# PCB-SSB-2x2.net
KiCad netlist of a schematic drawn in EAGLE
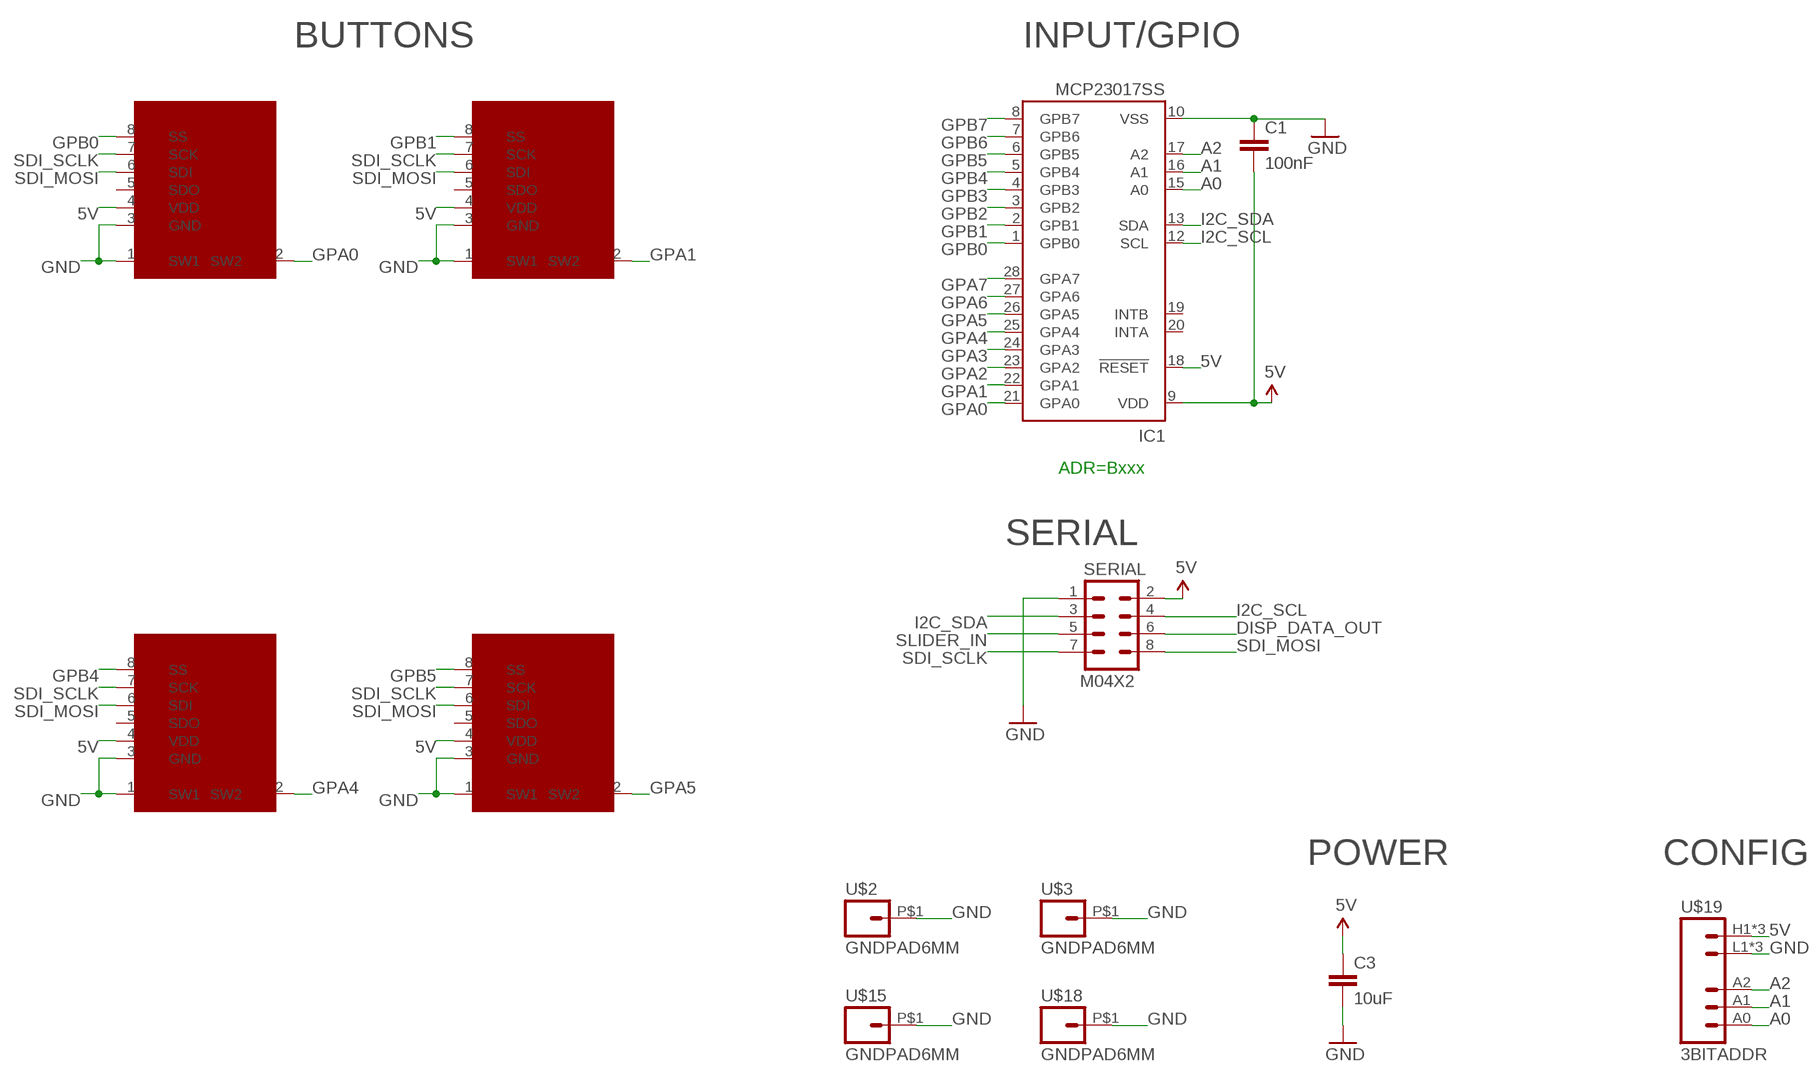
[diagram p0: schematic, sheet 1]

(export (version "E")
  (design (tool "Eeschema 10.0.6"))
  (components
    (comp (ref "C1")
      (value "100nF")
      (footprint "eagle-import:0603-CAP")
      (libsource (lib "eagle-import") (part "CAP0603-CAP"))
    )
    (comp (ref "C3")
      (value "10uF")
      (footprint "eagle-import:0805")
      (libsource (lib "eagle-import") (part "CAP0805"))
    )
    (comp (ref "IC1")
      (value "MCP23017SS")
      (footprint "eagle-import:SSOP28")
      (fields
        (field (name "MF") "MICROCHIP")
        (field (name "MPN") "MCP23017-E/SS")
        (field (name "MPN_1") "MCP23017-E/SS")
        (field (name "OC_FARNELL") "1467674")
        (field (name "OC_NEWARK") "31K2960")
      )
      (libsource (lib "eagle-import") (part "MCP23017SS"))
    )
    (comp (ref "SERIAL")
      (value "M04X2")
      (footprint "eagle-import:2X4")
      (libsource (lib "eagle-import") (part "M04X2"))
    )
    (comp (ref "SSW1")
      (value "SMART_SWITCHSMART_SWITCH_8PIN")
      (footprint "eagle-import:SMART_SWITCH")
      (libsource (lib "eagle-import") (part "SMART_SWITCHSMART_SWITCH_8PIN"))
    )
    (comp (ref "SSW2")
      (value "SMART_SWITCHSMART_SWITCH_8PIN")
      (footprint "eagle-import:SMART_SWITCH")
      (libsource (lib "eagle-import") (part "SMART_SWITCHSMART_SWITCH_8PIN"))
    )
    (comp (ref "SSW5")
      (value "SMART_SWITCHSMART_SWITCH_8PIN")
      (footprint "eagle-import:SMART_SWITCH")
      (libsource (lib "eagle-import") (part "SMART_SWITCHSMART_SWITCH_8PIN"))
    )
    (comp (ref "SSW6")
      (value "SMART_SWITCHSMART_SWITCH_8PIN")
      (footprint "eagle-import:SMART_SWITCH")
      (libsource (lib "eagle-import") (part "SMART_SWITCHSMART_SWITCH_8PIN"))
    )
    (comp (ref "U$2")
      (value "GNDPAD6MM")
      (footprint "eagle-import:3.2MMPAD6MM")
      (libsource (lib "eagle-import") (part "GNDPAD6MM"))
    )
    (comp (ref "U$3")
      (value "GNDPAD6MM")
      (footprint "eagle-import:3.2MMPAD6MM")
      (libsource (lib "eagle-import") (part "GNDPAD6MM"))
    )
    (comp (ref "U$15")
      (value "GNDPAD6MM")
      (footprint "eagle-import:3.2MMPAD6MM")
      (libsource (lib "eagle-import") (part "GNDPAD6MM"))
    )
    (comp (ref "U$18")
      (value "GNDPAD6MM")
      (footprint "eagle-import:3.2MMPAD6MM")
      (libsource (lib "eagle-import") (part "GNDPAD6MM"))
    )
    (comp (ref "U$19")
      (value "3BITADDR")
      (footprint "eagle-import:3BITADDR")
      (libsource (lib "eagle-import") (part "3BITADDR"))
    )
  )
  (nets
    (net (code "1") (name "/A0") (class "Default")
      (node (ref "IC1") (pin "15") (pinfunction "A0_15") (pintype "input"))
      (node (ref "U$19") (pin "A0") (pinfunction "A0_A0") (pintype "passive"))
    )
    (net (code "2") (name "/A1") (class "Default")
      (node (ref "IC1") (pin "16") (pinfunction "A1_16") (pintype "input"))
      (node (ref "U$19") (pin "A1") (pinfunction "A1_A1") (pintype "passive"))
    )
    (net (code "3") (name "/A2") (class "Default")
      (node (ref "IC1") (pin "17") (pinfunction "A2_17") (pintype "input"))
      (node (ref "U$19") (pin "A2") (pinfunction "A2_A2") (pintype "passive"))
    )
    (net (code "4") (name "/DISP_DATA_OUT") (class "Default")
      (node (ref "SERIAL") (pin "6") (pinfunction "6_6") (pintype "passive"))
    )
    (net (code "5") (name "/GPA0") (class "Default")
      (node (ref "IC1") (pin "21") (pinfunction "GPA0_21") (pintype "bidirectional"))
      (node (ref "SSW1") (pin "2") (pinfunction "SW2_2") (pintype "bidirectional"))
    )
    (net (code "6") (name "/GPA1") (class "Default")
      (node (ref "IC1") (pin "22") (pinfunction "GPA1_22") (pintype "bidirectional"))
      (node (ref "SSW2") (pin "2") (pinfunction "SW2_2") (pintype "bidirectional"))
    )
    (net (code "7") (name "/GPA2") (class "Default")
      (node (ref "IC1") (pin "23") (pinfunction "GPA2_23") (pintype "bidirectional"))
    )
    (net (code "8") (name "/GPA3") (class "Default")
      (node (ref "IC1") (pin "24") (pinfunction "GPA3_24") (pintype "bidirectional"))
    )
    (net (code "9") (name "/GPA4") (class "Default")
      (node (ref "IC1") (pin "25") (pinfunction "GPA4_25") (pintype "bidirectional"))
      (node (ref "SSW5") (pin "2") (pinfunction "SW2_2") (pintype "bidirectional"))
    )
    (net (code "10") (name "/GPA5") (class "Default")
      (node (ref "IC1") (pin "26") (pinfunction "GPA5_26") (pintype "bidirectional"))
      (node (ref "SSW6") (pin "2") (pinfunction "SW2_2") (pintype "bidirectional"))
    )
    (net (code "11") (name "/GPA6") (class "Default")
      (node (ref "IC1") (pin "27") (pinfunction "GPA6_27") (pintype "bidirectional"))
    )
    (net (code "12") (name "/GPA7") (class "Default")
      (node (ref "IC1") (pin "28") (pinfunction "GPA7_28") (pintype "bidirectional"))
    )
    (net (code "13") (name "/GPB0") (class "Default")
      (node (ref "IC1") (pin "1") (pinfunction "GPB0_1") (pintype "bidirectional"))
      (node (ref "SSW1") (pin "8") (pinfunction "SS_8") (pintype "bidirectional"))
    )
    (net (code "14") (name "/GPB1") (class "Default")
      (node (ref "IC1") (pin "2") (pinfunction "GPB1_2") (pintype "bidirectional"))
      (node (ref "SSW2") (pin "8") (pinfunction "SS_8") (pintype "bidirectional"))
    )
    (net (code "15") (name "/GPB2") (class "Default")
      (node (ref "IC1") (pin "3") (pinfunction "GPB2_3") (pintype "bidirectional"))
    )
    (net (code "16") (name "/GPB3") (class "Default")
      (node (ref "IC1") (pin "4") (pinfunction "GPB3_4") (pintype "bidirectional"))
    )
    (net (code "17") (name "/GPB4") (class "Default")
      (node (ref "IC1") (pin "5") (pinfunction "GPB4_5") (pintype "bidirectional"))
      (node (ref "SSW5") (pin "8") (pinfunction "SS_8") (pintype "bidirectional"))
    )
    (net (code "18") (name "/GPB5") (class "Default")
      (node (ref "IC1") (pin "6") (pinfunction "GPB5_6") (pintype "bidirectional"))
      (node (ref "SSW6") (pin "8") (pinfunction "SS_8") (pintype "bidirectional"))
    )
    (net (code "19") (name "/GPB6") (class "Default")
      (node (ref "IC1") (pin "7") (pinfunction "GPB6_7") (pintype "bidirectional"))
    )
    (net (code "20") (name "/GPB7") (class "Default")
      (node (ref "IC1") (pin "8") (pinfunction "GPB7_8") (pintype "bidirectional"))
    )
    (net (code "21") (name "/I2C_SCL") (class "Default")
      (node (ref "IC1") (pin "12") (pinfunction "SCL_12") (pintype "input"))
      (node (ref "SERIAL") (pin "4") (pinfunction "4_4") (pintype "passive"))
    )
    (net (code "22") (name "/I2C_SDA") (class "Default")
      (node (ref "IC1") (pin "13") (pinfunction "SDA_13") (pintype "bidirectional"))
      (node (ref "SERIAL") (pin "3") (pinfunction "3_3") (pintype "passive"))
    )
    (net (code "23") (name "/SDI_MOSI") (class "Default")
      (node (ref "SERIAL") (pin "8") (pinfunction "8_8") (pintype "passive"))
      (node (ref "SSW1") (pin "6") (pinfunction "SDI_6") (pintype "bidirectional"))
      (node (ref "SSW2") (pin "6") (pinfunction "SDI_6") (pintype "bidirectional"))
      (node (ref "SSW5") (pin "6") (pinfunction "SDI_6") (pintype "bidirectional"))
      (node (ref "SSW6") (pin "6") (pinfunction "SDI_6") (pintype "bidirectional"))
    )
    (net (code "24") (name "/SDI_SCLK") (class "Default")
      (node (ref "SERIAL") (pin "7") (pinfunction "7_7") (pintype "passive"))
      (node (ref "SSW1") (pin "7") (pinfunction "SCK_7") (pintype "bidirectional"))
      (node (ref "SSW2") (pin "7") (pinfunction "SCK_7") (pintype "bidirectional"))
      (node (ref "SSW5") (pin "7") (pinfunction "SCK_7") (pintype "bidirectional"))
      (node (ref "SSW6") (pin "7") (pinfunction "SCK_7") (pintype "bidirectional"))
    )
    (net (code "25") (name "/SLIDER_IN") (class "Default")
      (node (ref "SERIAL") (pin "5") (pinfunction "5_5") (pintype "passive"))
    )
    (net (code "26") (name "5V") (class "Default")
      (node (ref "C1") (pin "2") (pinfunction "2_2") (pintype "passive"))
      (node (ref "C3") (pin "1") (pinfunction "1_1") (pintype "passive"))
      (node (ref "IC1") (pin "18") (pinfunction "~{RESET}_18") (pintype "input"))
      (node (ref "IC1") (pin "9") (pinfunction "VDD_9") (pintype "power_in"))
      (node (ref "SERIAL") (pin "2") (pinfunction "2_2") (pintype "passive"))
      (node (ref "SSW1") (pin "4") (pinfunction "VDD_4") (pintype "bidirectional"))
      (node (ref "SSW2") (pin "4") (pinfunction "VDD_4") (pintype "bidirectional"))
      (node (ref "SSW5") (pin "4") (pinfunction "VDD_4") (pintype "bidirectional"))
      (node (ref "SSW6") (pin "4") (pinfunction "VDD_4") (pintype "bidirectional"))
      (node (ref "U$19") (pin "H1") (pinfunction "VCC_H1") (pintype "passive"))
      (node (ref "U$19") (pin "H2") (pinfunction "VCC_H2") (pintype "passive"))
      (node (ref "U$19") (pin "H3") (pinfunction "VCC_H3") (pintype "passive"))
    )
    (net (code "27") (name "GND") (class "Default")
      (node (ref "C1") (pin "1") (pinfunction "1_1") (pintype "passive"))
      (node (ref "C3") (pin "2") (pinfunction "2_2") (pintype "passive"))
      (node (ref "IC1") (pin "10") (pinfunction "VSS_10") (pintype "power_in"))
      (node (ref "SERIAL") (pin "1") (pinfunction "1_1") (pintype "passive"))
      (node (ref "SSW1") (pin "1") (pinfunction "SW1_1") (pintype "bidirectional"))
      (node (ref "SSW1") (pin "3") (pinfunction "GND_3") (pintype "bidirectional"))
      (node (ref "SSW2") (pin "1") (pinfunction "SW1_1") (pintype "bidirectional"))
      (node (ref "SSW2") (pin "3") (pinfunction "GND_3") (pintype "bidirectional"))
      (node (ref "SSW5") (pin "1") (pinfunction "SW1_1") (pintype "bidirectional"))
      (node (ref "SSW5") (pin "3") (pinfunction "GND_3") (pintype "bidirectional"))
      (node (ref "SSW6") (pin "1") (pinfunction "SW1_1") (pintype "bidirectional"))
      (node (ref "SSW6") (pin "3") (pinfunction "GND_3") (pintype "bidirectional"))
      (node (ref "U$15") (pin "P$1") (pinfunction "1_P$1") (pintype "passive"))
      (node (ref "U$18") (pin "P$1") (pinfunction "1_P$1") (pintype "passive"))
      (node (ref "U$19") (pin "L1") (pinfunction "GND_L1") (pintype "passive"))
      (node (ref "U$19") (pin "L2") (pinfunction "GND_L2") (pintype "passive"))
      (node (ref "U$19") (pin "L3") (pinfunction "GND_L3") (pintype "passive"))
      (node (ref "U$2") (pin "P$1") (pinfunction "1_P$1") (pintype "passive"))
      (node (ref "U$3") (pin "P$1") (pinfunction "1_P$1") (pintype "passive"))
    )
    (net (code "28") (name "unconnected-(IC1-INTA-Pad20)") (class "Default")
      (node (ref "IC1") (pin "20") (pinfunction "INTA_20") (pintype "output"))
    )
    (net (code "29") (name "unconnected-(IC1-INTB-Pad19)") (class "Default")
      (node (ref "IC1") (pin "19") (pinfunction "INTB_19") (pintype "output"))
    )
    (net (code "30") (name "unconnected-(SSW1-SDO-Pad5)") (class "Default")
      (node (ref "SSW1") (pin "5") (pinfunction "SDO_5") (pintype "bidirectional"))
    )
    (net (code "31") (name "unconnected-(SSW2-SDO-Pad5)") (class "Default")
      (node (ref "SSW2") (pin "5") (pinfunction "SDO_5") (pintype "bidirectional"))
    )
    (net (code "32") (name "unconnected-(SSW5-SDO-Pad5)") (class "Default")
      (node (ref "SSW5") (pin "5") (pinfunction "SDO_5") (pintype "bidirectional"))
    )
    (net (code "33") (name "unconnected-(SSW6-SDO-Pad5)") (class "Default")
      (node (ref "SSW6") (pin "5") (pinfunction "SDO_5") (pintype "bidirectional"))
    )
  )
)
